# 1uprava1.net
KiCad netlist of a schematic drawn in EAGLE
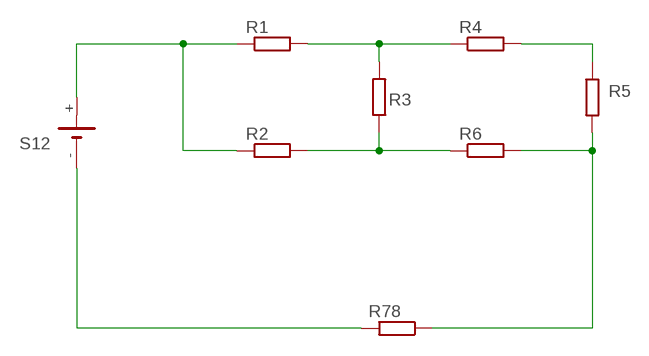
[diagram p0: schematic, sheet 1]

(export (version "E")
  (design (tool "Eeschema 10.0.6"))
  (components
    (comp (ref "R1")
      (value "680R")
      (footprint "eagle-import:0204_7")
      (libsource (lib "eagle-import") (part "R-EU_0204/7"))
    )
    (comp (ref "R2")
      (value "600R")
      (footprint "eagle-import:0204_7")
      (libsource (lib "eagle-import") (part "R-EU_0204/7"))
    )
    (comp (ref "R3")
      (value "260R")
      (footprint "eagle-import:0204_7")
      (libsource (lib "eagle-import") (part "R-EU_0204/7"))
    )
    (comp (ref "R4")
      (value "310R")
      (footprint "eagle-import:0204_7")
      (libsource (lib "eagle-import") (part "R-EU_0204/7"))
    )
    (comp (ref "R5")
      (value "575R")
      (footprint "eagle-import:0204_7")
      (libsource (lib "eagle-import") (part "R-EU_0204/7"))
    )
    (comp (ref "R6")
      (value "870R")
      (footprint "eagle-import:0204_7")
      (libsource (lib "eagle-import") (part "R-EU_0204/7"))
    )
    (comp (ref "R78")
      (value "355R")
      (footprint "eagle-import:0204_7")
      (libsource (lib "eagle-import") (part "R-EU_0204/7"))
    )
    (comp (ref "S12")
      (value "135V")
      (footprint "eagle-import:CH291-1220LF")
      (libsource (lib "eagle-import") (part "CH291-1220LF"))
    )
  )
  (nets
    (net (code "1") (name "Net-(R1-Pad1)") (class "Default")
      (node (ref "R1") (pin "1") (pinfunction "1_1") (pintype "passive"))
      (node (ref "R2") (pin "1") (pinfunction "1_1") (pintype "passive"))
      (node (ref "S12") (pin "+") (pinfunction "+_+") (pintype "passive"))
    )
    (net (code "2") (name "Net-(R1-Pad2)") (class "Default")
      (node (ref "R1") (pin "2") (pinfunction "2_2") (pintype "passive"))
      (node (ref "R3") (pin "2") (pinfunction "2_2") (pintype "passive"))
      (node (ref "R4") (pin "1") (pinfunction "1_1") (pintype "passive"))
    )
    (net (code "3") (name "Net-(R2-Pad2)") (class "Default")
      (node (ref "R2") (pin "2") (pinfunction "2_2") (pintype "passive"))
      (node (ref "R3") (pin "1") (pinfunction "1_1") (pintype "passive"))
      (node (ref "R6") (pin "1") (pinfunction "1_1") (pintype "passive"))
    )
    (net (code "4") (name "Net-(R4-Pad2)") (class "Default")
      (node (ref "R4") (pin "2") (pinfunction "2_2") (pintype "passive"))
      (node (ref "R5") (pin "1") (pinfunction "1_1") (pintype "passive"))
    )
    (net (code "5") (name "Net-(R5-Pad2)") (class "Default")
      (node (ref "R5") (pin "2") (pinfunction "2_2") (pintype "passive"))
      (node (ref "R6") (pin "2") (pinfunction "2_2") (pintype "passive"))
      (node (ref "R78") (pin "1") (pinfunction "1_1") (pintype "passive"))
    )
    (net (code "6") (name "Net-(R78-Pad2)") (class "Default")
      (node (ref "R78") (pin "2") (pinfunction "2_2") (pintype "passive"))
      (node (ref "S12") (pin "-") (pinfunction "-_-") (pintype "passive"))
    )
  )
)
